# Sensor_Box_CAN_Switch.net
KiCad netlist of a schematic drawn in Altium Designer
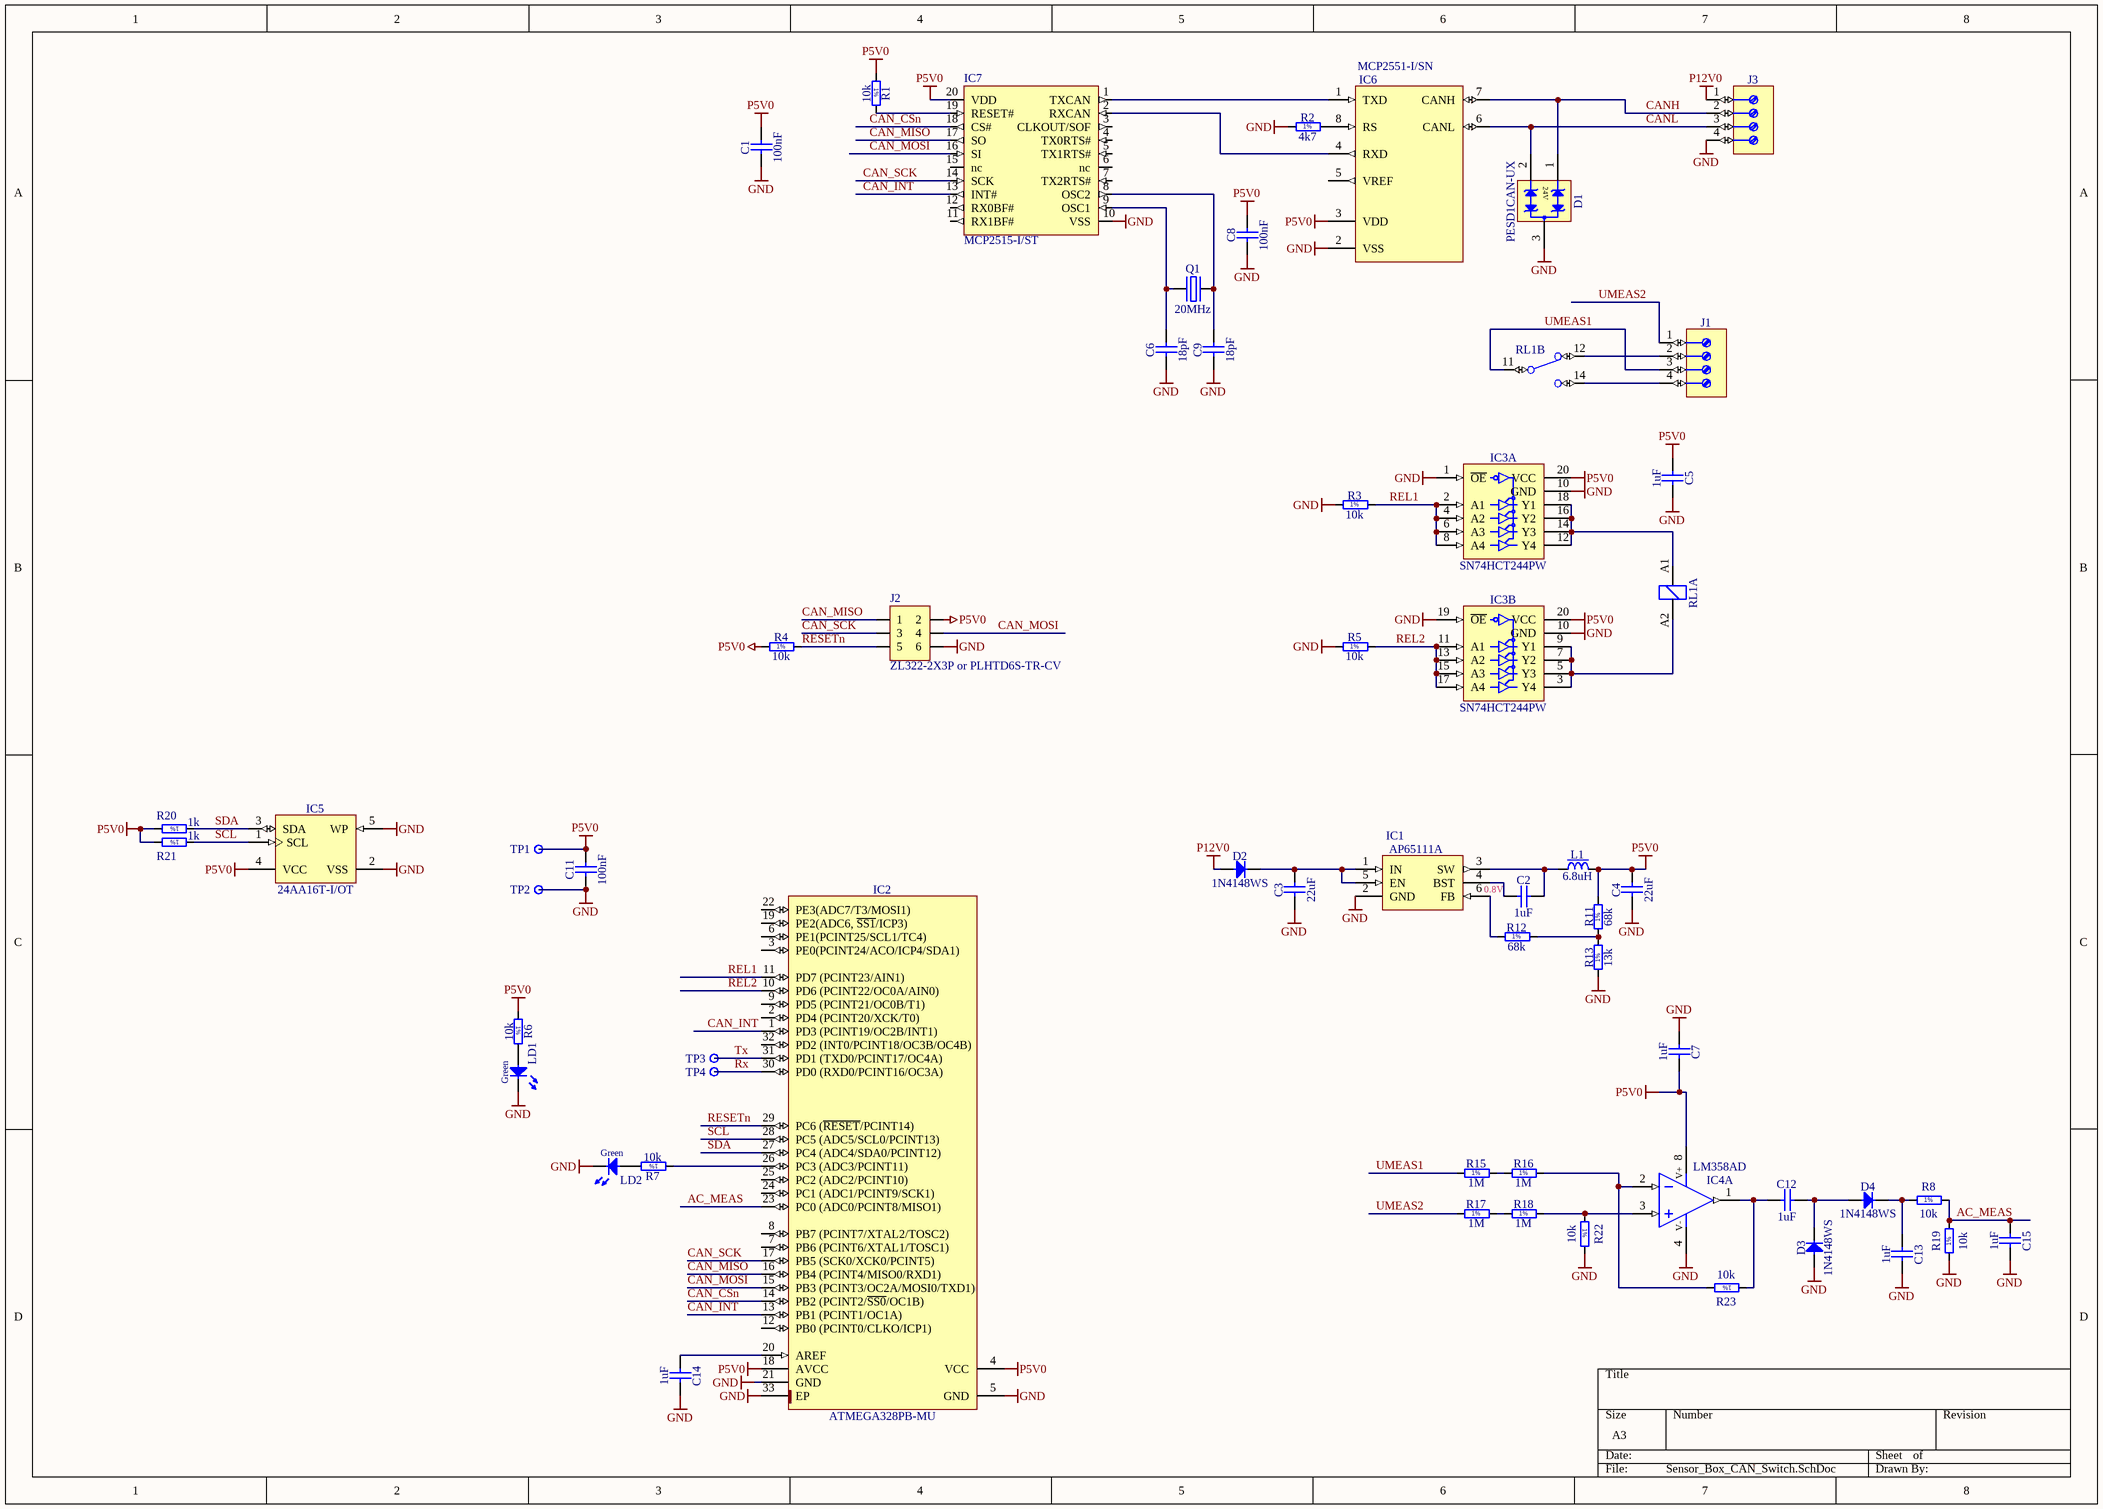
[diagram p0: Sensor_Box_CAN_Switch.SchDoc]

(export (version "E")
  (design (tool "Eeschema 10.0.6"))
  (components
    (comp (ref "C1")
      (value "100nF")
      (footprint "CAPC1005X55N")
      (description "Non-polarised capacitor")
      (fields
        (field (name "PART NUMBER") "CC0402_100NF_16V_10%_X5R")
        (field (name "VOLTAGE") "16V")
        (field (name "AUTHOR") "CERN DEM JLC")
      )
      (libsource (lib "Capacitors") (part "Capacitor - non polarized"))
    )
    (comp (ref "C2")
      (value "1uF")
      (footprint "CAPC1608X87N")
      (description "Non-polarised capacitor")
      (fields
        (field (name "PART NUMBER") "CC0603_1UF_16V_10%_X7R")
        (field (name "VOLTAGE") "16V")
        (field (name "AUTHOR") "CERN DEM JLC")
      )
      (libsource (lib "Capacitors") (part "Capacitor - non polarized"))
    )
    (comp (ref "C3")
      (value "22uF")
      (footprint "CAPC1709X100N")
      (description "Non-polarised capacitor")
      (fields
        (field (name "PART NUMBER") "CC0603_22UF_6.3V_20%_X5R")
        (field (name "VOLTAGE") "6.3V")
        (field (name "AUTHOR") "CERN DEM JLC")
      )
      (libsource (lib "Capacitors") (part "Capacitor - non polarized"))
    )
    (comp (ref "C4")
      (value "22uF")
      (footprint "CAPC1709X100N")
      (description "Non-polarised capacitor")
      (fields
        (field (name "PART NUMBER") "CC0603_22UF_6.3V_20%_X5R")
        (field (name "VOLTAGE") "6.3V")
        (field (name "AUTHOR") "CERN DEM JLC")
      )
      (libsource (lib "Capacitors") (part "Capacitor - non polarized"))
    )
    (comp (ref "C5")
      (value "1uF")
      (footprint "CAPC1005X55N")
      (description "Non-polarised capacitor")
      (fields
        (field (name "PART NUMBER") "CC0402_1UF_16V_10%_X5R")
        (field (name "VOLTAGE") "16V")
        (field (name "AUTHOR") "CERN DEM JLC")
      )
      (libsource (lib "Capacitors") (part "Capacitor - non polarized"))
    )
    (comp (ref "C6")
      (value "18pF")
      (footprint "CAPC1005X55N")
      (description "Non-polarised capacitor")
      (fields
        (field (name "PART NUMBER") "CC0402_18PF_50V_5%_C0G")
        (field (name "VOLTAGE") "50V")
        (field (name "AUTHOR") "CERN DEM JLC")
      )
      (libsource (lib "Capacitors") (part "Capacitor - non polarized"))
    )
    (comp (ref "C7")
      (value "1uF")
      (footprint "CAPC1005X55N")
      (description "Non-polarised capacitor")
      (fields
        (field (name "PART NUMBER") "CC0402_1UF_16V_10%_X5R")
        (field (name "VOLTAGE") "16V")
        (field (name "AUTHOR") "CERN DEM JLC")
      )
      (libsource (lib "Capacitors") (part "Capacitor - non polarized"))
    )
    (comp (ref "C8")
      (value "100nF")
      (footprint "CAPC1005X55N")
      (description "Non-polarised capacitor")
      (fields
        (field (name "PART NUMBER") "CC0402_100NF_16V_10%_X5R")
        (field (name "VOLTAGE") "16V")
        (field (name "AUTHOR") "CERN DEM JLC")
      )
      (libsource (lib "Capacitors") (part "Capacitor - non polarized"))
    )
    (comp (ref "C9")
      (value "18pF")
      (footprint "CAPC1005X55N")
      (description "Non-polarised capacitor")
      (fields
        (field (name "PART NUMBER") "CC0402_18PF_50V_5%_C0G")
        (field (name "VOLTAGE") "50V")
        (field (name "AUTHOR") "CERN DEM JLC")
      )
      (libsource (lib "Capacitors") (part "Capacitor - non polarized"))
    )
    (comp (ref "C11")
      (value "100nF")
      (footprint "CAPC1005X55N")
      (description "Non-polarised capacitor")
      (fields
        (field (name "PART NUMBER") "CC0402_100NF_16V_10%_X5R")
        (field (name "VOLTAGE") "16V")
        (field (name "AUTHOR") "CERN DEM JLC")
      )
      (libsource (lib "Capacitors") (part "Capacitor - non polarized"))
    )
    (comp (ref "C12")
      (value "1uF")
      (footprint "CAPC1005X55N")
      (description "Non-polarised capacitor")
      (fields
        (field (name "PART NUMBER") "CC0402_1UF_16V_10%_X5R")
        (field (name "VOLTAGE") "16V")
        (field (name "AUTHOR") "CERN DEM JLC")
      )
      (libsource (lib "Capacitors") (part "Capacitor - non polarized"))
    )
    (comp (ref "C13")
      (value "1uF")
      (footprint "CAPC1005X55N")
      (description "Non-polarised capacitor")
      (fields
        (field (name "PART NUMBER") "CC0402_1UF_16V_10%_X5R")
        (field (name "VOLTAGE") "16V")
        (field (name "AUTHOR") "CERN DEM JLC")
      )
      (libsource (lib "Capacitors") (part "Capacitor - non polarized"))
    )
    (comp (ref "C14")
      (value "1uF")
      (footprint "CAPC1005X55N")
      (description "Non-polarised capacitor")
      (fields
        (field (name "PART NUMBER") "CC0402_1UF_16V_10%_X5R")
        (field (name "VOLTAGE") "16V")
        (field (name "AUTHOR") "CERN DEM JLC")
      )
      (libsource (lib "Capacitors") (part "Capacitor - non polarized"))
    )
    (comp (ref "C15")
      (value "1uF")
      (footprint "CAPC1005X55N")
      (description "Non-polarised capacitor")
      (fields
        (field (name "PART NUMBER") "CC0402_1UF_16V_10%_X5R")
        (field (name "VOLTAGE") "16V")
        (field (name "AUTHOR") "CERN DEM JLC")
      )
      (libsource (lib "Capacitors") (part "Capacitor - non polarized"))
    )
    (comp (ref "D1")
      (value "PESD1CAN-UX")
      (footprint "SOT95P237X112-3N")
      (description "TVS Diode for CAN")
      (fields
        (field (name "VOLTAGE") "24V")
        (field (name "POWER") "400W")
        (field (name "AUTHOR") "CERN DEM JLC")
      )
      (libsource (lib "LIBRARY_SCH") (part "D_TVS_PESD1CAN"))
    )
    (comp (ref "D2")
      (value "1N4148WS")
      (footprint "SODFL2512X100N")
      (description "Diode")
      (fields
        (field (name "VOLTAGE") "75V")
        (field (name "POWER") "150mA")
        (field (name "AUTHOR") "CERN DEM JLC")
      )
      (libsource (lib "ICs And Semiconductors") (part "Diode"))
    )
    (comp (ref "D3")
      (value "1N4148WS")
      (footprint "SODFL2512X100N")
      (description "Diode")
      (fields
        (field (name "VOLTAGE") "75V")
        (field (name "POWER") "150mA")
        (field (name "AUTHOR") "CERN DEM JLC")
      )
      (libsource (lib "ICs And Semiconductors") (part "Diode"))
    )
    (comp (ref "D4")
      (value "1N4148WS")
      (footprint "SODFL2512X100N")
      (description "Diode")
      (fields
        (field (name "VOLTAGE") "75V")
        (field (name "POWER") "150mA")
        (field (name "AUTHOR") "CERN DEM JLC")
      )
      (libsource (lib "ICs And Semiconductors") (part "Diode"))
    )
    (comp (ref "IC1")
      (value "AP65111A")
      (footprint "SOT95P285X110-6N")
      (description "LIGHT LOAD IMPROVED 1.5A SYNCH DC/DC BUCK CONVERTER")
      (fields (field (name "MANUFACTURER") "DIODES INCORPORATED") (field (name "AUTHOR") "GK"))
      (libsource (lib "LIBRARY_SCH") (part "PM_AP65111A"))
    )
    (comp (ref "IC2")
      (value "ATMEGA328PB-MU")
      (footprint "QFN50P500X500X100-33N-S325")
      (description "8-bit AVR 20MHz Microcontroller With 32K Bytes In-System  Programmable  Flash")
      (fields (field (name "MANUFACTURER") "ATMEL") (field (name "AUTHOR") "GK"))
      (libsource (lib "LIBRARY_SCH") (part "UPC_ATMEGA328PB-MU"))
    )
    (comp (ref "IC3")
      (value "SN74HCT244PW")
      (footprint "SOP65P640X120-20N")
      (description "Octal Buffer/Driver with 3-State Ouputs")
      (fields (field (name "MANUFACTURER") "TEXAS INSTRUMENTS") (field (name "AUTHOR") "CERN DEM JLC"))
      (libsource (lib "ICs And Semiconductors") (part "74244_a"))
    )
    (comp (ref "IC4")
      (value "LM358AD")
      (footprint "SOIC127P600X175-8N")
      (description "Dual Operational Amplifier")
      (fields (field (name "MANUFACTURER") "TEXAS INSTRUMENTS") (field (name "AUTHOR") "CERN DEM JLC"))
      (libsource (lib "ICs And Semiconductors") (part "Operational Amplifier x2 Type1"))
    )
    (comp (ref "IC5")
      (value "24AA16T-I/OT")
      (footprint "SOT95P280X145-5N")
      (description "1.7V-5.5V, 2K I2C Serial EEPROM With EUI-48 Node Identity")
      (fields (field (name "MANUFACTURER") "MICROCHIP TECHNOLOGY") (field (name "AUTHOR") "GK"))
      (libsource (lib "LIBRARY_SCH") (part "MEM_24AA16T_SOT23"))
    )
    (comp (ref "IC6")
      (value "MCP2551-I/SN")
      (footprint "SOIC127P600X175-8N")
      (description "High-Speed CAN Transceiver, 8-Pin SOIC, Industrial Temperature")
      (fields (field (name "MANUFACTURER") "MICROCHIP TECHNOLOGY") (field (name "AUTHOR") "GK"))
      (libsource (lib "LIBRARY_SCH") (part "IFC_MCP2551"))
    )
    (comp (ref "IC7")
      (value "MCP2515-I/ST")
      (footprint "SOP65P640X110-20N")
      (description "CAN Controller With SPI nterface")
      (fields
        (field (name "MANUFACTURER") "Microchip")
        (field (name "MANUFACTURER PART NUMBER") "MCP2515T-I/ST")
      )
      (libsource (lib "LIBRARY_SCH") (part "IFC_MCP2515_TSSOP"))
    )
    (comp (ref "J1")
      (value "~")
      (footprint "TYCO_282836-4")
      (description "Terminal Block, 4 Positions, Screw Connection")
      (fields
        (field (name "PART NUMBER") "TYCO_282836-4")
        (field (name "MANUFACTURER") "TYCO ELECTRONICS")
        (field (name "AUTHOR") "CERN DEM JLC")
      )
      (libsource (lib "Connectors") (part "Terminal Block_4 Positions_Screw Connection"))
    )
    (comp (ref "J2")
      (value "ZL322-2X3P or PLHTD6S-TR-CV")
      (footprint "ZL322-2X3P")
      (description "1.27 mm dual row goldpin (Maritex)")
      (libsource (lib "LIBRARY_SCH") (part "CON_2x3 1.27 SMT Male"))
    )
    (comp (ref "J3")
      (value "~")
      (footprint "PHOENIX_1725672")
      (description "Terminal Block, 4 Positions, Screw Connection")
      (fields
        (field (name "PART NUMBER") "PHOENIX_1725672")
        (field (name "MANUFACTURER") "PHOENIX CONTACT")
        (field (name "AUTHOR") "CERN DEM JMW")
      )
      (libsource (lib "Connectors") (part "Terminal Block_4 Positions_Screw Connection"))
    )
    (comp (ref "L1")
      (value "6.8uH")
      (footprint "IND_WALSIN_WLPN3030")
      (description "6,8uH; 900mA; 0,211Ω; 3x3x1,5mm")
      (fields
        (field (name "PART NUMBER") "IND_6.8UH_20%_WALSIN_WLPN303015M6R8PB")
        (field (name "POWER") "900mA")
        (field (name "AUTHOR") "GK")
      )
      (libsource (lib "LIBRARY_SCH") (part "IND_WLPN3030"))
    )
    (comp (ref "LD1")
      (value "Green")
      (footprint "LED_KINGBRIGHT_KPH-1608CGCK")
      (description "LED Green 1C 2A")
      (fields
        (field (name "PART NUMBER") "LED_KINGBRIGHT_KPH-1608CGCK")
        (field (name "MANUFACTURER") "KINGBRIGHT")
        (field (name "AUTHOR") "CERN DEM JLC")
      )
      (libsource (lib "ICs And Semiconductors") (part "LED Green 1C 2A"))
    )
    (comp (ref "LD2")
      (value "Green")
      (footprint "LED_KINGBRIGHT_KPH-1608CGCK")
      (description "LED Green 1C 2A")
      (fields
        (field (name "PART NUMBER") "LED_KINGBRIGHT_KPH-1608CGCK")
        (field (name "MANUFACTURER") "KINGBRIGHT")
        (field (name "AUTHOR") "CERN DEM JLC")
      )
      (libsource (lib "ICs And Semiconductors") (part "LED Green 1C 2A"))
    )
    (comp (ref "Q1")
      (value "20MHz")
      (footprint "XTAL1160X490X430")
      (description "Quartz Crystal 20MHz, 30ppm, 20pF")
      (fields
        (field (name "PART NUMBER") "SR PASSIVES 20M-49SMD-SR")
        (field (name "MANUFACTURER") "SR PASSIVES")
        (field (name "AUTHOR") "GK")
      )
      (libsource (lib "LIBRARY_SCH") (part "X_CRYSTAL_20M_HC49"))
    )
    (comp (ref "R1")
      (value "10k")
      (footprint "RESC1005X40N")
      (description "Resistor - 1%")
      (fields
        (field (name "PART NUMBER") "R0402_10K_1%_0.0625W_100PPM")
        (field (name "POWER") "0.0625W")
        (field (name "AUTHOR") "CERN DEM JLC")
      )
      (libsource (lib "Resistors") (part "Resistor - 1%"))
    )
    (comp (ref "R2")
      (value "4k7")
      (footprint "RESC1005X40N")
      (description "Resistor - 1%")
      (fields
        (field (name "PART NUMBER") "R0402_4K7_1%_0.0625W_100PPM")
        (field (name "POWER") "0.0625W")
        (field (name "AUTHOR") "CERN DEM JLC")
      )
      (libsource (lib "Resistors") (part "Resistor - 1%"))
    )
    (comp (ref "R3")
      (value "10k")
      (footprint "RESC1005X40N")
      (description "Resistor - 1%")
      (fields
        (field (name "PART NUMBER") "R0402_10K_1%_0.0625W_100PPM")
        (field (name "POWER") "0.0625W")
        (field (name "AUTHOR") "CERN DEM JLC")
      )
      (libsource (lib "Resistors") (part "Resistor - 1%"))
    )
    (comp (ref "R4")
      (value "10k")
      (footprint "RESC1005X40N")
      (description "Resistor - 1%")
      (fields
        (field (name "PART NUMBER") "R0402_10K_1%_0.0625W_100PPM")
        (field (name "POWER") "0.0625W")
        (field (name "AUTHOR") "CERN DEM JLC")
      )
      (libsource (lib "Resistors") (part "Resistor - 1%"))
    )
    (comp (ref "R5")
      (value "10k")
      (footprint "RESC1005X40N")
      (description "Resistor - 1%")
      (fields
        (field (name "PART NUMBER") "R0402_10K_1%_0.0625W_100PPM")
        (field (name "POWER") "0.0625W")
        (field (name "AUTHOR") "CERN DEM JLC")
      )
      (libsource (lib "Resistors") (part "Resistor - 1%"))
    )
    (comp (ref "R6")
      (value "10k")
      (footprint "RESC1005X40N")
      (description "Resistor - 1%")
      (fields
        (field (name "PART NUMBER") "R0402_10K_1%_0.0625W_100PPM")
        (field (name "POWER") "0.0625W")
        (field (name "AUTHOR") "CERN DEM JLC")
      )
      (libsource (lib "Resistors") (part "Resistor - 1%"))
    )
    (comp (ref "R7")
      (value "10k")
      (footprint "RESC1005X40N")
      (description "Resistor - 1%")
      (fields
        (field (name "PART NUMBER") "R0402_10K_1%_0.0625W_100PPM")
        (field (name "POWER") "0.0625W")
        (field (name "AUTHOR") "CERN DEM JLC")
      )
      (libsource (lib "Resistors") (part "Resistor - 1%"))
    )
    (comp (ref "R8")
      (value "10k")
      (footprint "RESC1005X40N")
      (description "Resistor - 1%")
      (fields
        (field (name "PART NUMBER") "R0402_10K_1%_0.0625W_100PPM")
        (field (name "POWER") "0.0625W")
        (field (name "AUTHOR") "CERN DEM JLC")
      )
      (libsource (lib "Resistors") (part "Resistor - 1%"))
    )
    (comp (ref "R11")
      (value "68k")
      (footprint "RESC1005X40N")
      (description "Resistor - 1%")
      (fields
        (field (name "PART NUMBER") "R0402_68K_1%_0.0625W_100PPM")
        (field (name "POWER") "0.0625W")
        (field (name "AUTHOR") "CERN DEM JLC")
      )
      (libsource (lib "Resistors") (part "Resistor - 1%"))
    )
    (comp (ref "R12")
      (value "68k")
      (footprint "RESC1005X40N")
      (description "Resistor - 1%")
      (fields
        (field (name "PART NUMBER") "R0402_68K_1%_0.0625W_100PPM")
        (field (name "POWER") "0.0625W")
        (field (name "AUTHOR") "CERN DEM JLC")
      )
      (libsource (lib "Resistors") (part "Resistor - 1%"))
    )
    (comp (ref "R13")
      (value "13k")
      (footprint "RESC1005X40N")
      (description "Resistor - 1%")
      (fields
        (field (name "PART NUMBER") "R0402_13K_1%_0.0625W_100PPM")
        (field (name "POWER") "0.0625W")
        (field (name "AUTHOR") "CERN DEM JLC")
      )
      (libsource (lib "Resistors") (part "Resistor - 1%"))
    )
    (comp (ref "R15")
      (value "1M")
      (footprint "RESC3216X65N")
      (description "Resistor - 1%")
      (fields
        (field (name "PART NUMBER") "R1206_1M_1%_0.25W_100PPM")
        (field (name "POWER") "0.25W")
        (field (name "AUTHOR") "CERN DEM JLC")
      )
      (libsource (lib "Resistors") (part "Resistor - 1%"))
    )
    (comp (ref "R16")
      (value "1M")
      (footprint "RESC3216X65N")
      (description "Resistor - 1%")
      (fields
        (field (name "PART NUMBER") "R1206_1M_1%_0.25W_100PPM")
        (field (name "POWER") "0.25W")
        (field (name "AUTHOR") "CERN DEM JLC")
      )
      (libsource (lib "Resistors") (part "Resistor - 1%"))
    )
    (comp (ref "R17")
      (value "1M")
      (footprint "RESC3216X65N")
      (description "Resistor - 1%")
      (fields
        (field (name "PART NUMBER") "R1206_1M_1%_0.25W_100PPM")
        (field (name "POWER") "0.25W")
        (field (name "AUTHOR") "CERN DEM JLC")
      )
      (libsource (lib "Resistors") (part "Resistor - 1%"))
    )
    (comp (ref "R18")
      (value "1M")
      (footprint "RESC3216X65N")
      (description "Resistor - 1%")
      (fields
        (field (name "PART NUMBER") "R1206_1M_1%_0.25W_100PPM")
        (field (name "POWER") "0.25W")
        (field (name "AUTHOR") "CERN DEM JLC")
      )
      (libsource (lib "Resistors") (part "Resistor - 1%"))
    )
    (comp (ref "R19")
      (value "10k")
      (footprint "RESC1005X40N")
      (description "Resistor - 1%")
      (fields
        (field (name "PART NUMBER") "R0402_10K_1%_0.0625W_100PPM")
        (field (name "POWER") "0.0625W")
        (field (name "AUTHOR") "CERN DEM JLC")
      )
      (libsource (lib "Resistors") (part "Resistor - 1%"))
    )
    (comp (ref "R20")
      (value "1k")
      (footprint "RESC1005X40N")
      (description "Resistor - 1%")
      (fields
        (field (name "PART NUMBER") "R0402_1K_1%_0.0625W_100PPM")
        (field (name "POWER") "0.0625W")
        (field (name "AUTHOR") "CERN DEM JLC")
      )
      (libsource (lib "Resistors") (part "Resistor - 1%"))
    )
    (comp (ref "R21")
      (value "1k")
      (footprint "RESC1005X40N")
      (description "Resistor - 1%")
      (fields
        (field (name "PART NUMBER") "R0402_1K_1%_0.0625W_100PPM")
        (field (name "POWER") "0.0625W")
        (field (name "AUTHOR") "CERN DEM JLC")
      )
      (libsource (lib "Resistors") (part "Resistor - 1%"))
    )
    (comp (ref "R22")
      (value "10k")
      (footprint "RESC1005X40N")
      (description "Resistor - 1%")
      (fields
        (field (name "PART NUMBER") "R0402_10K_1%_0.0625W_100PPM")
        (field (name "POWER") "0.0625W")
        (field (name "AUTHOR") "CERN DEM JLC")
      )
      (libsource (lib "Resistors") (part "Resistor - 1%"))
    )
    (comp (ref "R23")
      (value "10k")
      (footprint "RESC1005X40N")
      (description "Resistor - 1%")
      (fields
        (field (name "PART NUMBER") "R0402_10K_1%_0.0625W_100PPM")
        (field (name "POWER") "0.0625W")
        (field (name "AUTHOR") "CERN DEM JLC")
      )
      (libsource (lib "Resistors") (part "Resistor - 1%"))
    )
    (comp (ref "RL1")
      (value "REL_TYCO_SCHRACK_PE014F05")
      (footprint "REL_TYCO_SCHRACK_PE")
      (description "PE PCB Relay Form C (1 CO Contact), 1 Coil")
      (fields
        (field (name "MANUFACTURER") "TYCO SCHRACK")
        (field (name "MANUFACTURER PART NUMBER") "PE014F05")
        (field (name "AUTHOR") "GK")
      )
      (libsource (lib "LIBRARY_SCH") (part "REL_TYCO_SCHRACK_PE014F05"))
    )
    (comp (ref "TP1")
      (value "Test Point")
      (footprint "TPS127")
      (fields (field (name "PART NUMBER") "SMD_PAD_1.27X1.27MM") (field (name "AUTHOR") "CERN DEM JLC"))
      (libsource (lib "Eletro-mechanical") (part "Test Point"))
    )
    (comp (ref "TP2")
      (value "Test Point")
      (footprint "TPS127")
      (fields (field (name "PART NUMBER") "SMD_PAD_1.27X1.27MM") (field (name "AUTHOR") "CERN DEM JLC"))
      (libsource (lib "Eletro-mechanical") (part "Test Point"))
    )
    (comp (ref "TP3")
      (value "Test Point")
      (footprint "TPS127")
      (fields (field (name "PART NUMBER") "SMD_PAD_1.27X1.27MM") (field (name "AUTHOR") "CERN DEM JLC"))
      (libsource (lib "Eletro-mechanical") (part "Test Point"))
    )
    (comp (ref "TP4")
      (value "Test Point")
      (footprint "TPS127")
      (fields (field (name "PART NUMBER") "SMD_PAD_1.27X1.27MM") (field (name "AUTHOR") "CERN DEM JLC"))
      (libsource (lib "Eletro-mechanical") (part "Test Point"))
    )
  )
  (nets
    (net (code "1") (name "/AC_MEAS") (class "Default")
      (node (ref "C15") (pin "1") (pinfunction "1_1") (pintype "passive"))
      (node (ref "IC2") (pin "23") (pinfunction "PC0_(ADC0/PCINT8/MISO1)_23") (pintype "bidirectional"))
      (node (ref "R19") (pin "2") (pinfunction "2_2") (pintype "passive"))
      (node (ref "R8") (pin "2") (pinfunction "2_2") (pintype "passive"))
    )
    (net (code "2") (name "/CANH") (class "Default")
      (node (ref "D1") (pin "1") (pinfunction "I/O1_1") (pintype "passive"))
      (node (ref "IC6") (pin "7") (pinfunction "CANH_7") (pintype "bidirectional"))
      (node (ref "J3") (pin "2") (pinfunction "2_2") (pintype "bidirectional"))
    )
    (net (code "3") (name "/CANL") (class "Default")
      (node (ref "D1") (pin "2") (pinfunction "I/O2_2") (pintype "passive"))
      (node (ref "IC6") (pin "6") (pinfunction "CANL_6") (pintype "bidirectional"))
      (node (ref "J3") (pin "3") (pinfunction "3_3") (pintype "bidirectional"))
    )
    (net (code "4") (name "/CAN_CSn") (class "Default")
      (node (ref "IC2") (pin "14") (pinfunction "PB2_(PCINT2/~{SS0}/OC1B)_14") (pintype "bidirectional"))
      (node (ref "IC7") (pin "18") (pinfunction "CS#_18") (pintype "output"))
    )
    (net (code "5") (name "/CAN_INT") (class "Default")
      (node (ref "IC2") (pin "1") (pinfunction "PD3_(PCINT19/OC2B/INT1)_1") (pintype "bidirectional"))
      (node (ref "IC2") (pin "13") (pinfunction "PB1_(PCINT1/OC1A)_13") (pintype "bidirectional"))
      (node (ref "IC7") (pin "13") (pinfunction "INT#_13") (pintype "output"))
    )
    (net (code "6") (name "/CAN_MISO") (class "Default")
      (node (ref "IC2") (pin "16") (pinfunction "PB4_(PCINT4/MISO0/RXD1)_16") (pintype "bidirectional"))
      (node (ref "IC7") (pin "17") (pinfunction "SO_17") (pintype "output"))
      (node (ref "J2") (pin "1") (pinfunction "1_1") (pintype "passive"))
    )
    (net (code "7") (name "/CAN_MOSI") (class "Default")
      (node (ref "IC2") (pin "15") (pinfunction "PB3_(PCINT3/OC2A/MOSI0/TXD1)_15") (pintype "bidirectional"))
      (node (ref "IC7") (pin "16") (pinfunction "SI_16") (pintype "input"))
      (node (ref "J2") (pin "4") (pinfunction "4_4") (pintype "passive"))
    )
    (net (code "8") (name "/CAN_SCK") (class "Default")
      (node (ref "IC2") (pin "17") (pinfunction "PB5_(SCK0/XCK0/PCINT5)_17") (pintype "bidirectional"))
      (node (ref "IC7") (pin "14") (pinfunction "SCK_14") (pintype "input"))
      (node (ref "J2") (pin "3") (pinfunction "3_3") (pintype "passive"))
    )
    (net (code "9") (name "/REL1") (class "Default")
      (node (ref "IC2") (pin "11") (pinfunction "PD7_(PCINT23/AIN1)_11") (pintype "bidirectional"))
      (node (ref "IC3") (pin "2") (pinfunction "A1_2") (pintype "input"))
      (node (ref "IC3") (pin "4") (pinfunction "A2_4") (pintype "input"))
      (node (ref "IC3") (pin "6") (pinfunction "A3_6") (pintype "input"))
      (node (ref "IC3") (pin "8") (pinfunction "A4_8") (pintype "input"))
      (node (ref "R3") (pin "2") (pinfunction "2_2") (pintype "passive"))
    )
    (net (code "10") (name "/REL2") (class "Default")
      (node (ref "IC2") (pin "10") (pinfunction "PD6_(PCINT22/OC0A/AIN0)_10") (pintype "bidirectional"))
      (node (ref "IC3") (pin "11") (pinfunction "A1_11") (pintype "input"))
      (node (ref "IC3") (pin "13") (pinfunction "A2_13") (pintype "input"))
      (node (ref "IC3") (pin "15") (pinfunction "A3_15") (pintype "input"))
      (node (ref "IC3") (pin "17") (pinfunction "A4_17") (pintype "input"))
      (node (ref "R5") (pin "2") (pinfunction "2_2") (pintype "passive"))
    )
    (net (code "11") (name "/RESETn") (class "Default")
      (node (ref "IC2") (pin "29") (pinfunction "PC6_(~{RESET}/PCINT14)_29") (pintype "bidirectional"))
      (node (ref "J2") (pin "5") (pinfunction "5_5") (pintype "passive"))
      (node (ref "R4") (pin "2") (pinfunction "2_2") (pintype "passive"))
    )
    (net (code "12") (name "/Rx") (class "Default")
      (node (ref "IC2") (pin "30") (pinfunction "PD0_(RXD0/PCINT16/OC3A)_30") (pintype "bidirectional"))
      (node (ref "TP4") (pin "1") (pinfunction "1_1") (pintype "bidirectional"))
    )
    (net (code "13") (name "/SCL") (class "Default")
      (node (ref "IC2") (pin "28") (pinfunction "PC5_(ADC5/SCL0/PCINT13)_28") (pintype "bidirectional"))
      (node (ref "IC5") (pin "1") (pinfunction "SCL_1") (pintype "input"))
      (node (ref "R21") (pin "1") (pinfunction "1_1") (pintype "passive"))
    )
    (net (code "14") (name "/SDA") (class "Default")
      (node (ref "IC2") (pin "27") (pinfunction "PC4_(ADC4/SDA0/PCINT12)_27") (pintype "bidirectional"))
      (node (ref "IC5") (pin "3") (pinfunction "SDA_3") (pintype "bidirectional"))
      (node (ref "R20") (pin "1") (pinfunction "1_1") (pintype "passive"))
    )
    (net (code "15") (name "/Tx") (class "Default")
      (node (ref "IC2") (pin "31") (pinfunction "PD1_(TXD0/PCINT17/OC4A)_31") (pintype "bidirectional"))
      (node (ref "TP3") (pin "1") (pinfunction "1_1") (pintype "bidirectional"))
    )
    (net (code "16") (name "/UMEAS1") (class "Default")
      (node (ref "J1") (pin "3") (pinfunction "3_3") (pintype "bidirectional"))
      (node (ref "R15") (pin "1") (pinfunction "1_1") (pintype "passive"))
      (node (ref "RL1") (pin "11") (pinfunction "C_11") (pintype "bidirectional"))
    )
    (net (code "17") (name "/UMEAS2") (class "Default")
      (node (ref "J1") (pin "1") (pinfunction "1_1") (pintype "bidirectional"))
      (node (ref "R17") (pin "1") (pinfunction "1_1") (pintype "passive"))
    )
    (net (code "18") (name "GND") (class "Default")
      (node (ref "C1") (pin "1") (pinfunction "1_1") (pintype "passive"))
      (node (ref "C11") (pin "1") (pinfunction "1_1") (pintype "passive"))
      (node (ref "C13") (pin "2") (pinfunction "2_2") (pintype "passive"))
      (node (ref "C14") (pin "2") (pinfunction "2_2") (pintype "passive"))
      (node (ref "C15") (pin "2") (pinfunction "2_2") (pintype "passive"))
      (node (ref "C3") (pin "1") (pinfunction "1_1") (pintype "passive"))
      (node (ref "C4") (pin "1") (pinfunction "1_1") (pintype "passive"))
      (node (ref "C5") (pin "2") (pinfunction "2_2") (pintype "passive"))
      (node (ref "C6") (pin "1") (pinfunction "1_1") (pintype "passive"))
      (node (ref "C7") (pin "1") (pinfunction "1_1") (pintype "passive"))
      (node (ref "C8") (pin "1") (pinfunction "1_1") (pintype "passive"))
      (node (ref "C9") (pin "1") (pinfunction "1_1") (pintype "passive"))
      (node (ref "D1") (pin "3") (pinfunction "GND_3") (pintype "passive"))
      (node (ref "D3") (pin "2") (pinfunction "A_2") (pintype "passive"))
      (node (ref "IC1") (pin "2") (pinfunction "GND_2") (pintype "power_in"))
      (node (ref "IC2") (pin "21") (pinfunction "GND_21") (pintype "power_in"))
      (node (ref "IC2") (pin "33") (pinfunction "EP_33") (pintype "power_in"))
      (node (ref "IC2") (pin "5") (pinfunction "GND_5") (pintype "power_in"))
      (node (ref "IC3") (pin "1") (pinfunction "~{OE}_1") (pintype "input"))
      (node (ref "IC3") (pin "10") (pinfunction "GND_10") (pintype "power_in"))
      (node (ref "IC3") (pin "19") (pinfunction "~{OE}_19") (pintype "input"))
      (node (ref "IC4") (pin "4") (pinfunction "V-_4") (pintype "power_in"))
      (node (ref "IC5") (pin "2") (pinfunction "VSS_2") (pintype "power_in"))
      (node (ref "IC5") (pin "5") (pinfunction "WP_5") (pintype "input"))
      (node (ref "IC6") (pin "2") (pinfunction "VSS_2") (pintype "power_in"))
      (node (ref "IC7") (pin "10") (pinfunction "VSS_10") (pintype "power_in"))
      (node (ref "J2") (pin "6") (pinfunction "6_6") (pintype "passive"))
      (node (ref "J3") (pin "4") (pinfunction "4_4") (pintype "bidirectional"))
      (node (ref "LD1") (pin "1") (pinfunction "C_1") (pintype "passive"))
      (node (ref "LD2") (pin "1") (pinfunction "C_1") (pintype "passive"))
      (node (ref "R13") (pin "1") (pinfunction "1_1") (pintype "passive"))
      (node (ref "R19") (pin "1") (pinfunction "1_1") (pintype "passive"))
      (node (ref "R2") (pin "1") (pinfunction "1_1") (pintype "passive"))
      (node (ref "R22") (pin "2") (pinfunction "2_2") (pintype "passive"))
      (node (ref "R3") (pin "1") (pinfunction "1_1") (pintype "passive"))
      (node (ref "R5") (pin "1") (pinfunction "1_1") (pintype "passive"))
      (node (ref "TP2") (pin "1") (pinfunction "1_1") (pintype "bidirectional"))
    )
    (net (code "19") (name "Net-(D2-C)") (class "Default")
      (node (ref "C3") (pin "2") (pinfunction "2_2") (pintype "passive"))
      (node (ref "D2") (pin "1") (pinfunction "C_1") (pintype "passive"))
      (node (ref "IC1") (pin "1") (pinfunction "IN_1") (pintype "input"))
      (node (ref "IC1") (pin "5") (pinfunction "EN_5") (pintype "input"))
    )
    (net (code "20") (name "Net-(D3-C)") (class "Default")
      (node (ref "C12") (pin "2") (pinfunction "2_2") (pintype "passive"))
      (node (ref "D3") (pin "1") (pinfunction "C_1") (pintype "passive"))
      (node (ref "D4") (pin "2") (pinfunction "A_2") (pintype "passive"))
    )
    (net (code "21") (name "Net-(D4-C)") (class "Default")
      (node (ref "C13") (pin "1") (pinfunction "1_1") (pintype "passive"))
      (node (ref "D4") (pin "1") (pinfunction "C_1") (pintype "passive"))
      (node (ref "R8") (pin "1") (pinfunction "1_1") (pintype "passive"))
    )
    (net (code "22") (name "Net-(IC1-BST)") (class "Default")
      (node (ref "C2") (pin "1") (pinfunction "1_1") (pintype "passive"))
      (node (ref "IC1") (pin "4") (pinfunction "BST_4") (pintype "passive"))
    )
    (net (code "23") (name "Net-(IC1-FB)") (class "Default")
      (node (ref "IC1") (pin "6") (pinfunction "FB_6") (pintype "input"))
      (node (ref "R12") (pin "1") (pinfunction "1_1") (pintype "passive"))
    )
    (net (code "24") (name "Net-(IC1-SW)") (class "Default")
      (node (ref "C2") (pin "2") (pinfunction "2_2") (pintype "passive"))
      (node (ref "IC1") (pin "3") (pinfunction "SW_3") (pintype "output"))
      (node (ref "L1") (pin "1") (pinfunction "1_1") (pintype "passive"))
    )
    (net (code "25") (name "Net-(IC2-AREF)") (class "Default")
      (node (ref "C14") (pin "1") (pinfunction "1_1") (pintype "passive"))
      (node (ref "IC2") (pin "20") (pinfunction "AREF_20") (pintype "input"))
    )
    (net (code "26") (name "Net-(IC2-PC3_(ADC3{slash}PCINT11))") (class "Default")
      (node (ref "IC2") (pin "26") (pinfunction "PC3_(ADC3/PCINT11)_26") (pintype "bidirectional"))
      (node (ref "R7") (pin "1") (pinfunction "1_1") (pintype "passive"))
    )
    (net (code "27") (name "Net-(IC3A-Y1)") (class "Default")
      (node (ref "IC3") (pin "12") (pinfunction "Y4_12") (pintype "tri_state"))
      (node (ref "IC3") (pin "14") (pinfunction "Y3_14") (pintype "tri_state"))
      (node (ref "IC3") (pin "16") (pinfunction "Y2_16") (pintype "tri_state"))
      (node (ref "IC3") (pin "18") (pinfunction "Y1_18") (pintype "tri_state"))
      (node (ref "RL1") (pin "A1") (pinfunction "A1_A1") (pintype "passive"))
    )
    (net (code "28") (name "Net-(IC3B-Y1)") (class "Default")
      (node (ref "IC3") (pin "3") (pinfunction "Y4_3") (pintype "tri_state"))
      (node (ref "IC3") (pin "5") (pinfunction "Y3_5") (pintype "tri_state"))
      (node (ref "IC3") (pin "7") (pinfunction "Y2_7") (pintype "tri_state"))
      (node (ref "IC3") (pin "9") (pinfunction "Y1_9") (pintype "tri_state"))
      (node (ref "RL1") (pin "A2") (pinfunction "A2_A2") (pintype "passive"))
    )
    (net (code "29") (name "Net-(IC4A-IN+)") (class "Default")
      (node (ref "IC4") (pin "3") (pinfunction "IN+_3") (pintype "input"))
      (node (ref "R18") (pin "2") (pinfunction "2_2") (pintype "passive"))
      (node (ref "R22") (pin "1") (pinfunction "1_1") (pintype "passive"))
    )
    (net (code "30") (name "Net-(IC4A-IN-)") (class "Default")
      (node (ref "IC4") (pin "2") (pinfunction "IN-_2") (pintype "input"))
      (node (ref "R16") (pin "2") (pinfunction "2_2") (pintype "passive"))
      (node (ref "R23") (pin "2") (pinfunction "2_2") (pintype "passive"))
    )
    (net (code "31") (name "Net-(IC4A-OUT)") (class "Default")
      (node (ref "C12") (pin "1") (pinfunction "1_1") (pintype "passive"))
      (node (ref "IC4") (pin "1") (pinfunction "OUT_1") (pintype "output"))
      (node (ref "R23") (pin "1") (pinfunction "1_1") (pintype "passive"))
    )
    (net (code "32") (name "Net-(IC6-RS)") (class "Default")
      (node (ref "IC6") (pin "8") (pinfunction "RS_8") (pintype "input"))
      (node (ref "R2") (pin "2") (pinfunction "2_2") (pintype "passive"))
    )
    (net (code "33") (name "Net-(IC6-RXD)") (class "Default")
      (node (ref "IC6") (pin "4") (pinfunction "RXD_4") (pintype "output"))
      (node (ref "IC7") (pin "2") (pinfunction "RXCAN_2") (pintype "input"))
    )
    (net (code "34") (name "Net-(IC6-TXD)") (class "Default")
      (node (ref "IC6") (pin "1") (pinfunction "TXD_1") (pintype "input"))
      (node (ref "IC7") (pin "1") (pinfunction "TXCAN_1") (pintype "output"))
    )
    (net (code "35") (name "Net-(IC7-OSC1)") (class "Default")
      (node (ref "C6") (pin "2") (pinfunction "2_2") (pintype "passive"))
      (node (ref "IC7") (pin "9") (pinfunction "OSC1_9") (pintype "input"))
      (node (ref "Q1") (pin "1") (pinfunction "OSC1_1") (pintype "passive"))
    )
    (net (code "36") (name "Net-(IC7-OSC2)") (class "Default")
      (node (ref "C9") (pin "2") (pinfunction "2_2") (pintype "passive"))
      (node (ref "IC7") (pin "8") (pinfunction "OSC2_8") (pintype "output"))
      (node (ref "Q1") (pin "2") (pinfunction "OSC2_2") (pintype "passive"))
    )
    (net (code "37") (name "Net-(IC7-RESET#)") (class "Default")
      (node (ref "IC7") (pin "19") (pinfunction "RESET#_19") (pintype "input"))
      (node (ref "R1") (pin "2") (pinfunction "2_2") (pintype "passive"))
    )
    (net (code "38") (name "Net-(LD1-A)") (class "Default")
      (node (ref "LD1") (pin "2") (pinfunction "A_2") (pintype "passive"))
      (node (ref "R6") (pin "2") (pinfunction "2_2") (pintype "passive"))
    )
    (net (code "39") (name "Net-(LD2-A)") (class "Default")
      (node (ref "LD2") (pin "2") (pinfunction "A_2") (pintype "passive"))
      (node (ref "R7") (pin "2") (pinfunction "2_2") (pintype "passive"))
    )
    (net (code "40") (name "Net-(R11-Pad1)") (class "Default")
      (node (ref "R11") (pin "1") (pinfunction "1_1") (pintype "passive"))
      (node (ref "R12") (pin "2") (pinfunction "2_2") (pintype "passive"))
      (node (ref "R13") (pin "2") (pinfunction "2_2") (pintype "passive"))
    )
    (net (code "41") (name "Net-(R15-Pad2)") (class "Default")
      (node (ref "R15") (pin "2") (pinfunction "2_2") (pintype "passive"))
      (node (ref "R16") (pin "1") (pinfunction "1_1") (pintype "passive"))
    )
    (net (code "42") (name "Net-(R17-Pad2)") (class "Default")
      (node (ref "R17") (pin "2") (pinfunction "2_2") (pintype "passive"))
      (node (ref "R18") (pin "1") (pinfunction "1_1") (pintype "passive"))
    )
    (net (code "43") (name "Net-(RL1B-NC)") (class "Default")
      (node (ref "J1") (pin "2") (pinfunction "2_2") (pintype "bidirectional"))
      (node (ref "RL1") (pin "12") (pinfunction "NC_12") (pintype "bidirectional"))
    )
    (net (code "44") (name "Net-(RL1B-NO)") (class "Default")
      (node (ref "J1") (pin "4") (pinfunction "4_4") (pintype "bidirectional"))
      (node (ref "RL1") (pin "14") (pinfunction "NO_14") (pintype "bidirectional"))
    )
    (net (code "45") (name "P5V0") (class "Default")
      (node (ref "C1") (pin "2") (pinfunction "2_2") (pintype "passive"))
      (node (ref "C11") (pin "2") (pinfunction "2_2") (pintype "passive"))
      (node (ref "C4") (pin "2") (pinfunction "2_2") (pintype "passive"))
      (node (ref "C5") (pin "1") (pinfunction "1_1") (pintype "passive"))
      (node (ref "C7") (pin "2") (pinfunction "2_2") (pintype "passive"))
      (node (ref "C8") (pin "2") (pinfunction "2_2") (pintype "passive"))
      (node (ref "IC2") (pin "18") (pinfunction "AVCC_18") (pintype "power_in"))
      (node (ref "IC2") (pin "4") (pinfunction "VCC_4") (pintype "power_in"))
      (node (ref "IC3") (pin "20") (pinfunction "VCC_20") (pintype "power_in"))
      (node (ref "IC4") (pin "8") (pinfunction "V+_8") (pintype "power_in"))
      (node (ref "IC5") (pin "4") (pinfunction "VCC_4") (pintype "power_in"))
      (node (ref "IC6") (pin "3") (pinfunction "VDD_3") (pintype "power_in"))
      (node (ref "IC7") (pin "20") (pinfunction "VDD_20") (pintype "power_in"))
      (node (ref "J2") (pin "2") (pinfunction "2_2") (pintype "passive"))
      (node (ref "L1") (pin "2") (pinfunction "2_2") (pintype "passive"))
      (node (ref "R1") (pin "1") (pinfunction "1_1") (pintype "passive"))
      (node (ref "R11") (pin "2") (pinfunction "2_2") (pintype "passive"))
      (node (ref "R20") (pin "2") (pinfunction "2_2") (pintype "passive"))
      (node (ref "R21") (pin "2") (pinfunction "2_2") (pintype "passive"))
      (node (ref "R4") (pin "1") (pinfunction "1_1") (pintype "passive"))
      (node (ref "R6") (pin "1") (pinfunction "1_1") (pintype "passive"))
      (node (ref "TP1") (pin "1") (pinfunction "1_1") (pintype "bidirectional"))
    )
    (net (code "46") (name "P12V0") (class "Default")
      (node (ref "D2") (pin "2") (pinfunction "A_2") (pintype "passive"))
      (node (ref "J3") (pin "1") (pinfunction "1_1") (pintype "bidirectional"))
    )
    (net (code "47") (name "unconnected-(IC2-PB0_(PCINT0{slash}CLKO{slash}ICP1)-Pad12)") (class "Default")
      (node (ref "IC2") (pin "12") (pinfunction "PB0_(PCINT0/CLKO/ICP1)_12") (pintype "bidirectional"))
    )
    (net (code "48") (name "unconnected-(IC2-PB6_(PCINT6{slash}XTAL1{slash}TOSC1)-Pad7)") (class "Default")
      (node (ref "IC2") (pin "7") (pinfunction "PB6_(PCINT6/XTAL1/TOSC1)_7") (pintype "bidirectional"))
    )
    (net (code "49") (name "unconnected-(IC2-PB7_(PCINT7{slash}XTAL2{slash}TOSC2)-Pad8)") (class "Default")
      (node (ref "IC2") (pin "8") (pinfunction "PB7_(PCINT7/XTAL2/TOSC2)_8") (pintype "bidirectional"))
    )
    (net (code "50") (name "unconnected-(IC2-PC1_(ADC1{slash}PCINT9{slash}SCK1)-Pad24)") (class "Default")
      (node (ref "IC2") (pin "24") (pinfunction "PC1_(ADC1/PCINT9/SCK1)_24") (pintype "bidirectional"))
    )
    (net (code "51") (name "unconnected-(IC2-PC2_(ADC2{slash}PCINT10)-Pad25)") (class "Default")
      (node (ref "IC2") (pin "25") (pinfunction "PC2_(ADC2/PCINT10)_25") (pintype "bidirectional"))
    )
    (net (code "52") (name "unconnected-(IC2-PD2_(INT0{slash}PCINT18{slash}OC3B{slash}OC4B)-Pad32)") (class "Default")
      (node (ref "IC2") (pin "32") (pinfunction "PD2_(INT0/PCINT18/OC3B/OC4B)_32") (pintype "bidirectional"))
    )
    (net (code "53") (name "unconnected-(IC2-PD4_(PCINT20{slash}XCK{slash}T0)-Pad2)") (class "Default")
      (node (ref "IC2") (pin "2") (pinfunction "PD4_(PCINT20/XCK/T0)_2") (pintype "bidirectional"))
    )
    (net (code "54") (name "unconnected-(IC2-PD5_(PCINT21{slash}OC0B{slash}T1)-Pad9)") (class "Default")
      (node (ref "IC2") (pin "9") (pinfunction "PD5_(PCINT21/OC0B/T1)_9") (pintype "bidirectional"))
    )
    (net (code "55") (name "unconnected-(IC2-PE0(PCINT24{slash}ACO{slash}ICP4{slash}SDA1)-Pad3)") (class "Default")
      (node (ref "IC2") (pin "3") (pinfunction "PE0(PCINT24/ACO/ICP4/SDA1)_3") (pintype "bidirectional"))
    )
    (net (code "56") (name "unconnected-(IC2-PE1(PCINT25{slash}SCL1{slash}TC4)-Pad6)") (class "Default")
      (node (ref "IC2") (pin "6") (pinfunction "PE1(PCINT25/SCL1/TC4)_6") (pintype "bidirectional"))
    )
    (net (code "57") (name "unconnected-(IC2-PE2(ADC6,_~{SS1}{slash}ICP3)-Pad19)") (class "Default")
      (node (ref "IC2") (pin "19") (pinfunction "PE2(ADC6,_~{SS1}/ICP3)_19") (pintype "bidirectional"))
    )
    (net (code "58") (name "unconnected-(IC2-PE3(ADC7{slash}T3{slash}MOSI1)-Pad22)") (class "Default")
      (node (ref "IC2") (pin "22") (pinfunction "PE3(ADC7/T3/MOSI1)_22") (pintype "bidirectional"))
    )
    (net (code "59") (name "unconnected-(IC6-VREF-Pad5)") (class "Default")
      (node (ref "IC6") (pin "5") (pinfunction "VREF_5") (pintype "output"))
    )
    (net (code "60") (name "unconnected-(IC7-CLKOUT{slash}SOF-Pad3)") (class "Default")
      (node (ref "IC7") (pin "3") (pinfunction "CLKOUT/SOF_3") (pintype "output"))
    )
    (net (code "61") (name "unconnected-(IC7-RX0BF#-Pad12)") (class "Default")
      (node (ref "IC7") (pin "12") (pinfunction "RX0BF#_12") (pintype "output"))
    )
    (net (code "62") (name "unconnected-(IC7-RX1BF#-Pad11)") (class "Default")
      (node (ref "IC7") (pin "11") (pinfunction "RX1BF#_11") (pintype "output"))
    )
    (net (code "63") (name "unconnected-(IC7-TX0RTS#-Pad4)") (class "Default")
      (node (ref "IC7") (pin "4") (pinfunction "TX0RTS#_4") (pintype "input"))
    )
    (net (code "64") (name "unconnected-(IC7-TX1RTS#-Pad5)") (class "Default")
      (node (ref "IC7") (pin "5") (pinfunction "TX1RTS#_5") (pintype "input"))
    )
    (net (code "65") (name "unconnected-(IC7-TX2RTS#-Pad7)") (class "Default")
      (node (ref "IC7") (pin "7") (pinfunction "TX2RTS#_7") (pintype "input"))
    )
    (net (code "66") (name "unconnected-(IC7-nc-Pad6)") (class "Default")
      (node (ref "IC7") (pin "6") (pinfunction "nc_6") (pintype "passive"))
    )
    (net (code "67") (name "unconnected-(IC7-nc-Pad15)") (class "Default")
      (node (ref "IC7") (pin "15") (pinfunction "nc_15") (pintype "passive"))
    )
  )
)
